# Sheet1.net
KiCad netlist of a schematic drawn in Altium Designer
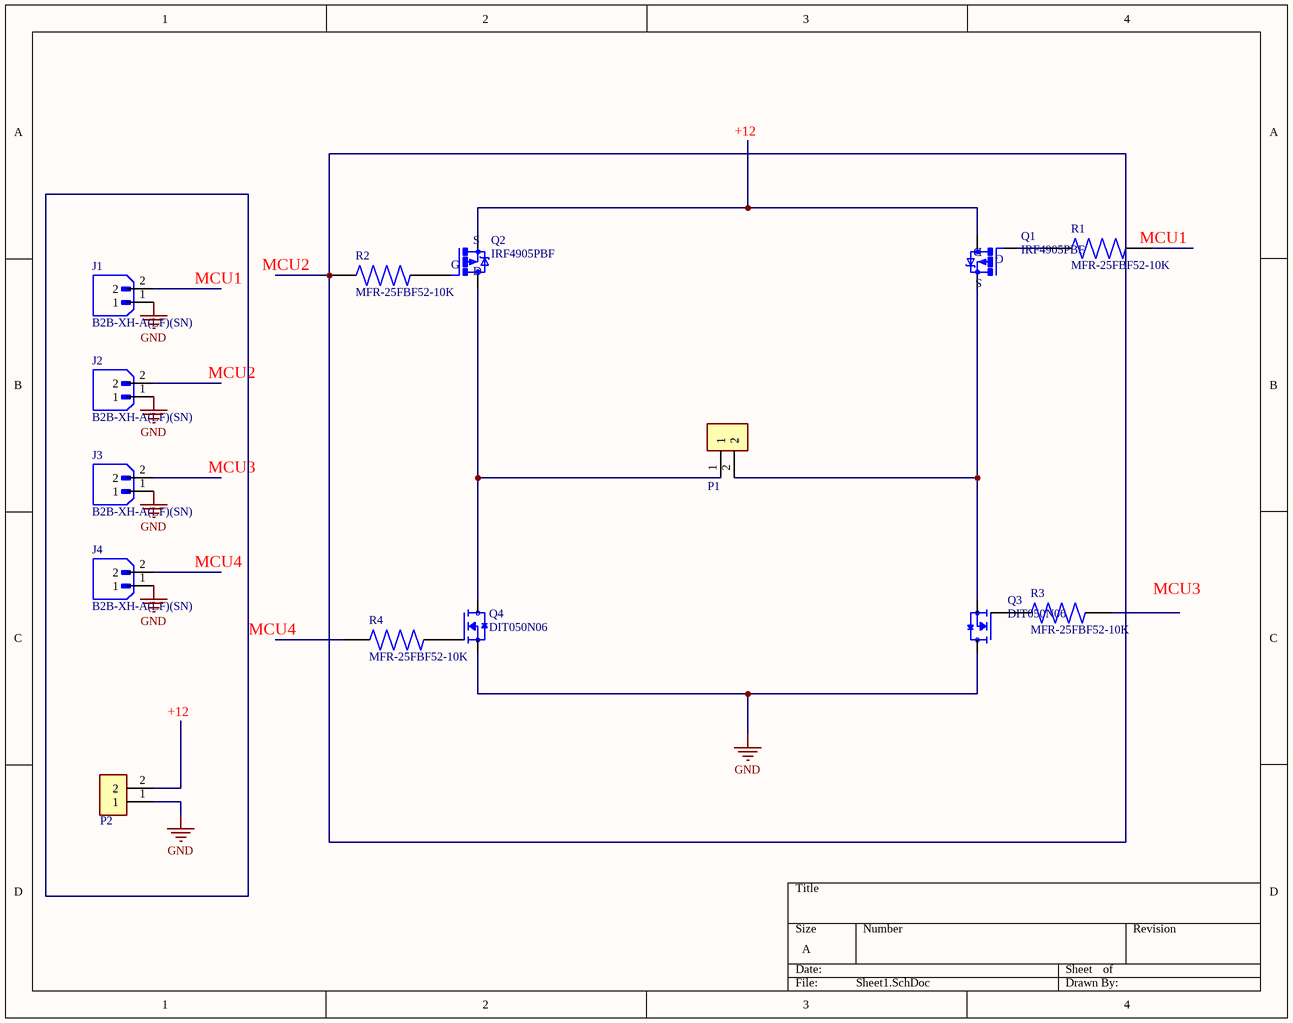
[diagram p0: Sheet1.SchDoc]

(export (version "E")
  (design (tool "Eeschema 10.0.6"))
  (components
    (comp (ref "J1")
      (value "B2B-XH-A(LF)(SN)")
      (footprint "JST_B2B-XH-A(LF)(SN)")
      (description "Connector Header Through Hole 2 position 0.098 (2.50mm)")
      (fields (field (name "MF") "JST Sales America Inc."))
      (libsource (lib "B2B-XH-A_LF__SN_") (part "B2B-XH-A(LF)(SN)"))
    )
    (comp (ref "J2")
      (value "B2B-XH-A(LF)(SN)")
      (footprint "JST_B2B-XH-A(LF)(SN)")
      (description "Connector Header Through Hole 2 position 0.098 (2.50mm)")
      (fields (field (name "MF") "JST Sales America Inc."))
      (libsource (lib "B2B-XH-A_LF__SN_") (part "B2B-XH-A(LF)(SN)"))
    )
    (comp (ref "J3")
      (value "B2B-XH-A(LF)(SN)")
      (footprint "JST_B2B-XH-A(LF)(SN)")
      (description "Connector Header Through Hole 2 position 0.098 (2.50mm)")
      (fields (field (name "MF") "JST Sales America Inc."))
      (libsource (lib "B2B-XH-A_LF__SN_") (part "B2B-XH-A(LF)(SN)"))
    )
    (comp (ref "J4")
      (value "B2B-XH-A(LF)(SN)")
      (footprint "JST_B2B-XH-A(LF)(SN)")
      (description "Connector Header Through Hole 2 position 0.098 (2.50mm)")
      (fields (field (name "MF") "JST Sales America Inc."))
      (libsource (lib "B2B-XH-A_LF__SN_") (part "B2B-XH-A(LF)(SN)"))
    )
    (comp (ref "P1")
      (value "282837-2")
      (footprint "TE_282837-2")
      (fields (field (name "MF") "TE Connectivity"))
      (libsource (lib "") (part "282837-2_1"))
    )
    (comp (ref "P2")
      (value "282837-2")
      (footprint "TE_282837-2")
      (fields (field (name "MF") "TE Connectivity"))
      (libsource (lib "282837-2") (part "282837-2"))
    )
    (comp (ref "Q1")
      (value "IRF4905PBF")
      (footprint "TO220BH")
      (description "P-Channel 55 V 74A (Tc) 200W (Tc) Through Hole TO-220AB")
      (fields (field (name "MF") "Infineon"))
      (libsource (lib "IRF4905PBF") (part "IRF4905PBF"))
    )
    (comp (ref "Q2")
      (value "IRF4905PBF")
      (footprint "TO220BH")
      (description "P-Channel 55 V 74A (Tc) 200W (Tc) Through Hole TO-220AB")
      (fields (field (name "MF") "Infineon"))
      (libsource (lib "") (part "IRF4905PBF_1"))
    )
    (comp (ref "Q3")
      (value "DIT050N06")
      (footprint "TO254P1010X450X1980-3B")
      (libsource (lib "DIT050N06") (part "DIT050N06"))
    )
    (comp (ref "Q4")
      (value "DIT050N06")
      (footprint "TO254P1010X450X1980-3B")
      (libsource (lib "DIT050N06") (part "DIT050N06"))
    )
    (comp (ref "R1")
      (value "MFR-25FBF52-10K")
      (footprint "RESAD1100W55L680D260")
      (description "10.2 kOhms Â±1% 0.25W, 1/4W Through Hole Resistor Axial - Metal Film")
      (fields (field (name "MF") "Yageo"))
      (libsource (lib "MFR-25FBF52-10K") (part "MFR-25FBF52-10K"))
    )
    (comp (ref "R2")
      (value "MFR-25FBF52-10K")
      (footprint "RESAD1100W55L680D260")
      (description "10.2 kOhms Â±1% 0.25W, 1/4W Through Hole Resistor Axial - Metal Film")
      (fields (field (name "MF") "Yageo"))
      (libsource (lib "MFR-25FBF52-10K") (part "MFR-25FBF52-10K"))
    )
    (comp (ref "R3")
      (value "MFR-25FBF52-10K")
      (footprint "RESAD1100W55L680D260")
      (description "10.2 kOhms Â±1% 0.25W, 1/4W Through Hole Resistor Axial - Metal Film")
      (fields (field (name "MF") "Yageo"))
      (libsource (lib "MFR-25FBF52-10K") (part "MFR-25FBF52-10K"))
    )
    (comp (ref "R4")
      (value "MFR-25FBF52-10K")
      (footprint "RESAD1100W55L680D260")
      (description "10.2 kOhms Â±1% 0.25W, 1/4W Through Hole Resistor Axial - Metal Film")
      (fields (field (name "MF") "Yageo"))
      (libsource (lib "MFR-25FBF52-10K") (part "MFR-25FBF52-10K"))
    )
  )
  (nets
    (net (code "1") (name "GND") (class "Default")
      (node (ref "J1") (pin "1") (pinfunction "1_1") (pintype "passive"))
      (node (ref "J2") (pin "1") (pinfunction "1_1") (pintype "passive"))
      (node (ref "J3") (pin "1") (pinfunction "1_1") (pintype "passive"))
      (node (ref "J4") (pin "1") (pinfunction "1_1") (pintype "passive"))
      (node (ref "P2") (pin "1") (pinfunction "1_1") (pintype "passive"))
      (node (ref "Q3") (pin "2") (pinfunction "D_2") (pintype "passive"))
      (node (ref "Q4") (pin "3") (pinfunction "S_3") (pintype "passive"))
    )
    (net (code "2") (name "Net-(Q1-PadD)") (class "Default")
      (node (ref "Q1") (pin "D") (pinfunction "D_D") (pintype "passive"))
      (node (ref "Q2") (pin "S") (pinfunction "S_S") (pintype "passive"))
    )
    (net (code "3") (name "Net-(Q1-PadG)") (class "Default")
      (node (ref "Q1") (pin "G") (pinfunction "G_G") (pintype "passive"))
      (node (ref "R1") (pin "1") (pinfunction "1_1") (pintype "passive"))
    )
    (net (code "4") (name "Net-(Q2-PadG)") (class "Default")
      (node (ref "Q2") (pin "G") (pinfunction "G_G") (pintype "passive"))
      (node (ref "R2") (pin "2") (pinfunction "2_2") (pintype "passive"))
    )
    (net (code "5") (name "Net-(Q3-G)") (class "Default")
      (node (ref "Q3") (pin "1") (pinfunction "G_1") (pintype "passive"))
      (node (ref "R3") (pin "1") (pinfunction "1_1") (pintype "passive"))
    )
    (net (code "6") (name "Net-(Q3-S)") (class "Default")
      (node (ref "P1") (pin "2") (pinfunction "2_2") (pintype "passive"))
      (node (ref "Q1") (pin "S") (pinfunction "S_S") (pintype "passive"))
      (node (ref "Q3") (pin "3") (pinfunction "S_3") (pintype "passive"))
    )
    (net (code "7") (name "Net-(Q4-D)") (class "Default")
      (node (ref "P1") (pin "1") (pinfunction "1_1") (pintype "passive"))
      (node (ref "Q2") (pin "D") (pinfunction "D_D") (pintype "passive"))
      (node (ref "Q4") (pin "2") (pinfunction "D_2") (pintype "passive"))
    )
    (net (code "8") (name "Net-(Q4-G)") (class "Default")
      (node (ref "Q4") (pin "1") (pinfunction "G_1") (pintype "passive"))
      (node (ref "R4") (pin "2") (pinfunction "2_2") (pintype "passive"))
    )
    (net (code "9") (name "unconnected-(J1-Pad2)") (class "Default")
      (node (ref "J1") (pin "2") (pinfunction "2_2") (pintype "passive"))
    )
    (net (code "10") (name "unconnected-(J2-Pad2)") (class "Default")
      (node (ref "J2") (pin "2") (pinfunction "2_2") (pintype "passive"))
    )
    (net (code "11") (name "unconnected-(J3-Pad2)") (class "Default")
      (node (ref "J3") (pin "2") (pinfunction "2_2") (pintype "passive"))
    )
    (net (code "12") (name "unconnected-(J4-Pad2)") (class "Default")
      (node (ref "J4") (pin "2") (pinfunction "2_2") (pintype "passive"))
    )
    (net (code "13") (name "unconnected-(P2-Pad2)") (class "Default")
      (node (ref "P2") (pin "2") (pinfunction "2_2") (pintype "passive"))
    )
    (net (code "14") (name "unconnected-(R1-Pad2)") (class "Default")
      (node (ref "R1") (pin "2") (pinfunction "2_2") (pintype "passive"))
    )
    (net (code "15") (name "unconnected-(R2-Pad1)") (class "Default")
      (node (ref "R2") (pin "1") (pinfunction "1_1") (pintype "passive"))
    )
    (net (code "16") (name "unconnected-(R3-Pad2)") (class "Default")
      (node (ref "R3") (pin "2") (pinfunction "2_2") (pintype "passive"))
    )
    (net (code "17") (name "unconnected-(R4-Pad1)") (class "Default")
      (node (ref "R4") (pin "1") (pinfunction "1_1") (pintype "passive"))
    )
  )
)
